# alarm_clock_devkit_usb_power.net
KiCad netlist of a schematic drawn in Altium Designer
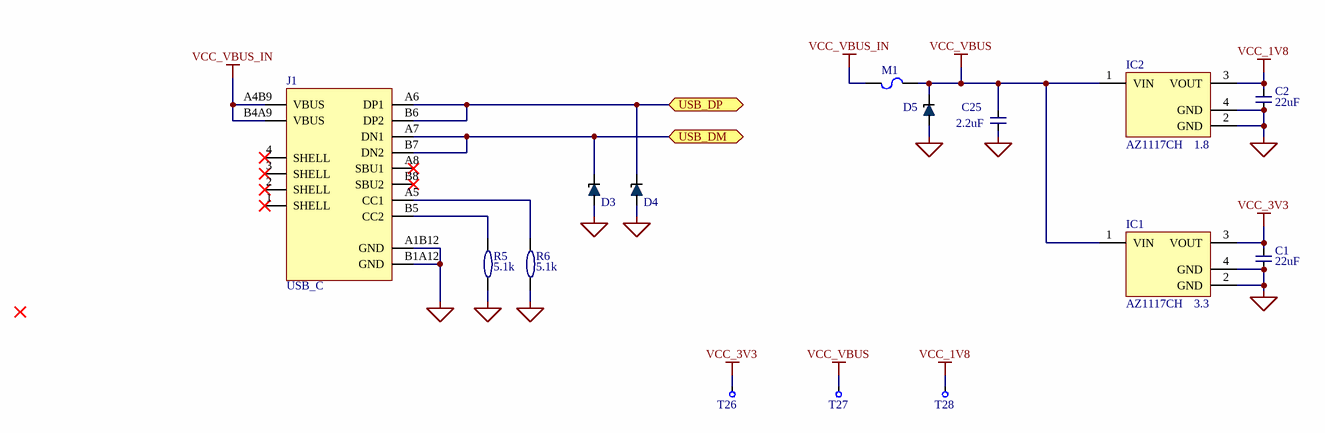
[diagram p0: alarm_clock_devkit_usb_power.SchDoc]

(export (version "E")
  (design (tool "Eeschema 10.0.6"))
  (components
    (comp (ref "C1")
      (value "22uF")
      (footprint "CAP 0805_2012")
      (description "MLCC")
      (libsource (lib "wifi_alarm_clock") (part "CAP_CERAMIC"))
    )
    (comp (ref "C2")
      (value "22uF")
      (footprint "CAP 0805_2012")
      (description "MLCC")
      (libsource (lib "wifi_alarm_clock") (part "CAP_CERAMIC"))
    )
    (comp (ref "C25")
      (value "2.2uF")
      (footprint "CAP 0805_2012")
      (description "MLCC")
      (libsource (lib "wifi_alarm_clock") (part "CAP_CERAMIC"))
    )
    (comp (ref "D3")
      (value "TVS_DIODE")
      (footprint "SODFL98X40-2L")
      (libsource (lib "wifi_alarm_clock") (part "TVS_DIODE"))
    )
    (comp (ref "D4")
      (value "TVS_DIODE")
      (footprint "SODFL98X40-2L")
      (libsource (lib "wifi_alarm_clock") (part "TVS_DIODE"))
    )
    (comp (ref "D5")
      (value "TVS_DIODE")
      (footprint "SODFL98X40-2L")
      (libsource (lib "wifi_alarm_clock") (part "TVS_DIODE"))
    )
    (comp (ref "IC1")
      (value "AZ1117CH")
      (footprint "SOT230P700X180-4N")
      (fields (field (name "VOUT") "3.3"))
      (libsource (lib "wifi_alarm_clock") (part "AZ1117CH"))
    )
    (comp (ref "IC2")
      (value "AZ1117CH")
      (footprint "SOT230P700X180-4N")
      (fields (field (name "VOUT") "1.8"))
      (libsource (lib "wifi_alarm_clock") (part "AZ1117CH"))
    )
    (comp (ref "J1")
      (value "USB_C")
      (footprint "USB-C-SMD_G-SWITCH_GT-USB-7010ASV")
      (libsource (lib "wifi_alarm_clock") (part "USB_C"))
    )
    (comp (ref "M1")
      (value "FUSE")
      (footprint "FUSE 0603_1608 0.5MM")
      (libsource (lib "wifi_alarm_clock") (part "FUSE"))
    )
    (comp (ref "R5")
      (value "5.1k")
      (footprint "RES 0603_1608")
      (description "Resistor")
      (libsource (lib "wifi_alarm_clock") (part "RESISTOR"))
    )
    (comp (ref "R6")
      (value "5.1k")
      (footprint "RES 0603_1608")
      (description "Resistor")
      (libsource (lib "wifi_alarm_clock") (part "RESISTOR"))
    )
    (comp (ref "T26")
      (value "TESTPOINT")
      (footprint "TESTPOINT_1MM")
      (libsource (lib "wifi_alarm_clock") (part "TESTPOINT"))
    )
    (comp (ref "T27")
      (value "TESTPOINT")
      (footprint "TESTPOINT_1MM")
      (libsource (lib "wifi_alarm_clock") (part "TESTPOINT"))
    )
    (comp (ref "T28")
      (value "TESTPOINT")
      (footprint "TESTPOINT_1MM")
      (libsource (lib "wifi_alarm_clock") (part "TESTPOINT"))
    )
  )
  (nets
    (net (code "1") (name "/USB_DM") (class "Default")
      (node (ref "D3") (pin "1") (pinfunction "K_1") (pintype "passive"))
      (node (ref "J1") (pin "A7") (pinfunction "DN1_A7") (pintype "passive"))
      (node (ref "J1") (pin "B7") (pinfunction "DN2_B7") (pintype "passive"))
    )
    (net (code "2") (name "/USB_DP") (class "Default")
      (node (ref "D4") (pin "1") (pinfunction "K_1") (pintype "passive"))
      (node (ref "J1") (pin "A6") (pinfunction "DP1_A6") (pintype "passive"))
      (node (ref "J1") (pin "B6") (pinfunction "DP2_B6") (pintype "passive"))
    )
    (net (code "3") (name "GND") (class "Default")
      (node (ref "C1") (pin "1") (pinfunction "A_1") (pintype "passive"))
      (node (ref "C2") (pin "1") (pinfunction "A_1") (pintype "passive"))
      (node (ref "C25") (pin "1") (pinfunction "A_1") (pintype "passive"))
      (node (ref "D3") (pin "2") (pinfunction "A_2") (pintype "passive"))
      (node (ref "D4") (pin "2") (pinfunction "A_2") (pintype "passive"))
      (node (ref "D5") (pin "2") (pinfunction "A_2") (pintype "passive"))
      (node (ref "IC1") (pin "2") (pinfunction "GND_2") (pintype "passive"))
      (node (ref "IC1") (pin "4") (pinfunction "GND_4") (pintype "passive"))
      (node (ref "IC2") (pin "2") (pinfunction "GND_2") (pintype "passive"))
      (node (ref "IC2") (pin "4") (pinfunction "GND_4") (pintype "passive"))
      (node (ref "J1") (pin "A1B12") (pinfunction "GND_A1B12") (pintype "passive"))
      (node (ref "J1") (pin "B1A12") (pinfunction "GND_B1A12") (pintype "passive"))
      (node (ref "R5") (pin "1") (pinfunction "A_1") (pintype "passive"))
      (node (ref "R6") (pin "1") (pinfunction "A_1") (pintype "passive"))
    )
    (net (code "4") (name "Net-(J1-CC1)") (class "Default")
      (node (ref "J1") (pin "A5") (pinfunction "CC1_A5") (pintype "passive"))
      (node (ref "R6") (pin "2") (pinfunction "B_2") (pintype "passive"))
    )
    (net (code "5") (name "Net-(J1-CC2)") (class "Default")
      (node (ref "J1") (pin "B5") (pinfunction "CC2_B5") (pintype "passive"))
      (node (ref "R5") (pin "2") (pinfunction "B_2") (pintype "passive"))
    )
    (net (code "6") (name "VCC_1V8") (class "Default")
      (node (ref "C2") (pin "2") (pinfunction "B_2") (pintype "passive"))
      (node (ref "IC2") (pin "3") (pinfunction "VOUT_3") (pintype "passive"))
      (node (ref "T28") (pin "1") (pintype "passive"))
    )
    (net (code "7") (name "VCC_3V3") (class "Default")
      (node (ref "C1") (pin "2") (pinfunction "B_2") (pintype "passive"))
      (node (ref "IC1") (pin "3") (pinfunction "VOUT_3") (pintype "passive"))
      (node (ref "T26") (pin "1") (pintype "passive"))
    )
    (net (code "8") (name "VCC_VBUS") (class "Default")
      (node (ref "C25") (pin "2") (pinfunction "B_2") (pintype "passive"))
      (node (ref "D5") (pin "1") (pinfunction "K_1") (pintype "passive"))
      (node (ref "IC1") (pin "1") (pinfunction "VIN_1") (pintype "passive"))
      (node (ref "IC2") (pin "1") (pinfunction "VIN_1") (pintype "passive"))
      (node (ref "M1") (pin "2") (pinfunction "2_2") (pintype "passive"))
      (node (ref "T27") (pin "1") (pintype "passive"))
    )
    (net (code "9") (name "VCC_VBUS_IN") (class "Default")
      (node (ref "J1") (pin "A4B9") (pinfunction "VBUS_A4B9") (pintype "passive"))
      (node (ref "J1") (pin "B4A9") (pinfunction "VBUS_B4A9") (pintype "passive"))
      (node (ref "M1") (pin "1") (pinfunction "1_1") (pintype "passive"))
    )
    (net (code "10") (name "unconnected-(J1-SBU1-PadA8)") (class "Default")
      (node (ref "J1") (pin "A8") (pinfunction "SBU1_A8") (pintype "passive+no_connect"))
    )
    (net (code "11") (name "unconnected-(J1-SBU2-PadB8)") (class "Default")
      (node (ref "J1") (pin "B8") (pinfunction "SBU2_B8") (pintype "passive+no_connect"))
    )
    (net (code "12") (name "unconnected-(J1-SHELL-Pad1)") (class "Default")
      (node (ref "J1") (pin "1") (pinfunction "SHELL_1") (pintype "passive+no_connect"))
    )
    (net (code "13") (name "unconnected-(J1-SHELL-Pad2)") (class "Default")
      (node (ref "J1") (pin "2") (pinfunction "SHELL_2") (pintype "passive+no_connect"))
    )
    (net (code "14") (name "unconnected-(J1-SHELL-Pad3)") (class "Default")
      (node (ref "J1") (pin "3") (pinfunction "SHELL_3") (pintype "passive+no_connect"))
    )
    (net (code "15") (name "unconnected-(J1-SHELL-Pad4)") (class "Default")
      (node (ref "J1") (pin "4") (pinfunction "SHELL_4") (pintype "passive+no_connect"))
    )
  )
)
